# Test.net
KiCad netlist of a schematic drawn in EAGLE
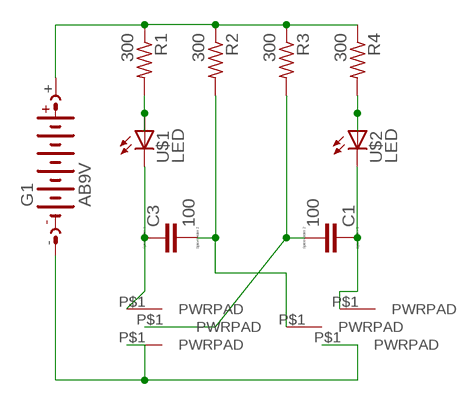
[diagram p0: schematic, sheet 1]

(export (version "E")
  (design (tool "Eeschema 10.0.6"))
  (components
    (comp (ref "C1")
      (value "100")
      (footprint "eagle-import:C1206")
      (libsource (lib "eagle-import") (part "CC1206"))
    )
    (comp (ref "C3")
      (value "100")
      (footprint "eagle-import:C1206")
      (libsource (lib "eagle-import") (part "CC1206"))
    )
    (comp (ref "G1")
      (value "AB9V")
      (footprint "eagle-import:AB9V")
      (libsource (lib "eagle-import") (part "AB9V"))
    )
    (comp (ref "J1")
      (value "PWRPAD2-5MM")
      (footprint "eagle-import:PWRPAD_2-5MM")
      (libsource (lib "eagle-import") (part "PWRPAD2-5MM"))
    )
    (comp (ref "J2")
      (value "PWRPAD2-5MM")
      (footprint "eagle-import:PWRPAD_2-5MM")
      (libsource (lib "eagle-import") (part "PWRPAD2-5MM"))
    )
    (comp (ref "J3")
      (value "PWRPAD2-5MM")
      (footprint "eagle-import:PWRPAD_2-5MM")
      (libsource (lib "eagle-import") (part "PWRPAD2-5MM"))
    )
    (comp (ref "J4")
      (value "PWRPAD2-5MM")
      (footprint "eagle-import:PWRPAD_2-5MM")
      (libsource (lib "eagle-import") (part "PWRPAD2-5MM"))
    )
    (comp (ref "J5")
      (value "PWRPAD2-5MM")
      (footprint "eagle-import:PWRPAD_2-5MM")
      (libsource (lib "eagle-import") (part "PWRPAD2-5MM"))
    )
    (comp (ref "J6")
      (value "PWRPAD2-5MM")
      (footprint "eagle-import:PWRPAD_2-5MM")
      (libsource (lib "eagle-import") (part "PWRPAD2-5MM"))
    )
    (comp (ref "R1")
      (value "300")
      (footprint "eagle-import:R1206")
      (libsource (lib "eagle-import") (part "RES-US1206"))
    )
    (comp (ref "R2")
      (value "300")
      (footprint "eagle-import:R1206")
      (libsource (lib "eagle-import") (part "RES-US1206"))
    )
    (comp (ref "R3")
      (value "300")
      (footprint "eagle-import:R1206")
      (libsource (lib "eagle-import") (part "RES-US1206"))
    )
    (comp (ref "R4")
      (value "300")
      (footprint "eagle-import:R1206")
      (libsource (lib "eagle-import") (part "RES-US1206"))
    )
    (comp (ref "U$1")
      (value "LED")
      (footprint "eagle-import:LED1206")
      (libsource (lib "eagle-import") (part "LED"))
    )
    (comp (ref "U$2")
      (value "LED")
      (footprint "eagle-import:LED1206")
      (libsource (lib "eagle-import") (part "LED"))
    )
  )
  (nets
    (net (code "1") (name "Net-(G1-Pad+)") (class "Default")
      (node (ref "G1") (pin "+") (pinfunction "+_+") (pintype "passive"))
      (node (ref "R1") (pin "1") (pinfunction "1_1") (pintype "passive"))
      (node (ref "R2") (pin "1") (pinfunction "1_1") (pintype "passive"))
      (node (ref "R3") (pin "1") (pinfunction "1_1") (pintype "passive"))
      (node (ref "R4") (pin "1") (pinfunction "1_1") (pintype "passive"))
    )
    (net (code "2") (name "Net-(J1-PWRPAD)") (class "Default")
      (node (ref "G1") (pin "-") (pinfunction "-_-") (pintype "passive"))
      (node (ref "J1") (pin "P$1") (pinfunction "PWRPAD_P$1") (pintype "bidirectional"))
      (node (ref "J6") (pin "P$1") (pinfunction "PWRPAD_P$1") (pintype "bidirectional"))
    )
    (net (code "3") (name "Net-(J2-PWRPAD)") (class "Default")
      (node (ref "C1") (pin "2") (pinfunction "2_2") (pintype "passive"))
      (node (ref "J2") (pin "P$1") (pinfunction "PWRPAD_P$1") (pintype "bidirectional"))
      (node (ref "R3") (pin "2") (pinfunction "2_2") (pintype "passive"))
    )
    (net (code "4") (name "Net-(J3-PWRPAD)") (class "Default")
      (node (ref "C3") (pin "1") (pinfunction "1_1") (pintype "passive"))
      (node (ref "J3") (pin "P$1") (pinfunction "PWRPAD_P$1") (pintype "bidirectional"))
      (node (ref "U$1") (pin "2") (pinfunction "C_2") (pintype "passive"))
    )
    (net (code "5") (name "Net-(J4-PWRPAD)") (class "Default")
      (node (ref "C3") (pin "2") (pinfunction "2_2") (pintype "passive"))
      (node (ref "J4") (pin "P$1") (pinfunction "PWRPAD_P$1") (pintype "bidirectional"))
      (node (ref "R2") (pin "2") (pinfunction "2_2") (pintype "passive"))
    )
    (net (code "6") (name "Net-(J5-PWRPAD)") (class "Default")
      (node (ref "C1") (pin "1") (pinfunction "1_1") (pintype "passive"))
      (node (ref "J5") (pin "P$1") (pinfunction "PWRPAD_P$1") (pintype "bidirectional"))
      (node (ref "U$2") (pin "2") (pinfunction "C_2") (pintype "passive"))
    )
    (net (code "7") (name "Net-(U$1-A)") (class "Default")
      (node (ref "R1") (pin "2") (pinfunction "2_2") (pintype "passive"))
      (node (ref "U$1") (pin "1") (pinfunction "A_1") (pintype "passive"))
    )
    (net (code "8") (name "Net-(U$2-A)") (class "Default")
      (node (ref "R4") (pin "2") (pinfunction "2_2") (pintype "passive"))
      (node (ref "U$2") (pin "1") (pinfunction "A_1") (pintype "passive"))
    )
  )
)
